# PowerSystem.net
KiCad netlist of a schematic drawn in Altium Designer
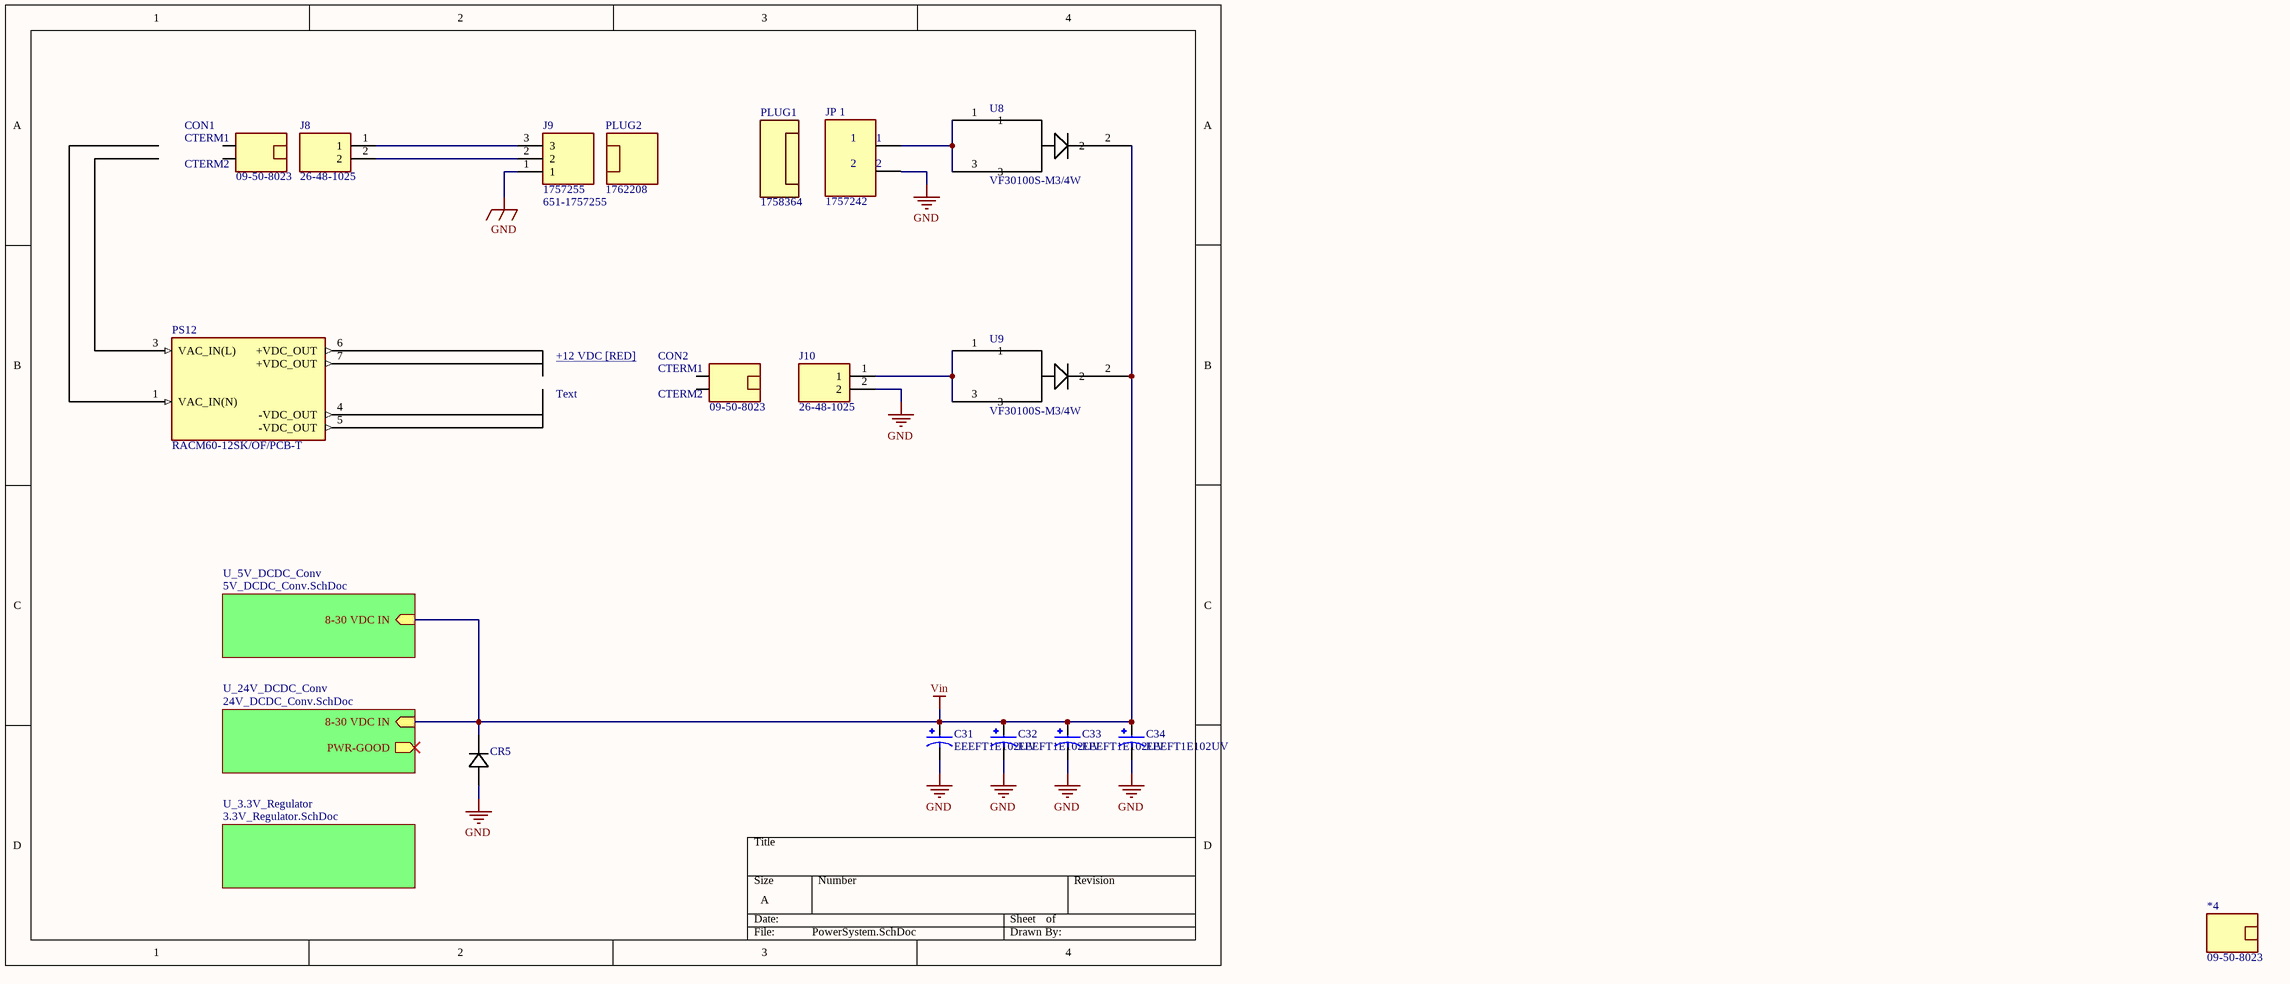
[diagram p0: PowerSystem.SchDoc]

(export (version "E")
  (design (tool "Eeschema 10.0.6"))
  (components
    (comp (ref "*4")
      (value "09-50-8023")
      (footprint "Connector_09-50-8023")
      (description "Connector Housing Receptacle 2 Position 3.96mm Straight Bag")
      (fields (field (name "MANUFACTURER") "Molex"))
      (libsource (lib "") (part "09-50-8023_1"))
    )
    (comp (ref "C31")
      (value "EEEFT1E102UV")
      (footprint "CAP_EEEFT1E102UV")
      (fields (field (name "MP") "EEE-FT1E102UV") (field (name "MF") "Panasonic Electronic Components"))
      (libsource (lib "EEEFT1E102UV") (part "EEEFT1E102UV"))
    )
    (comp (ref "C32")
      (value "EEEFT1E102UV")
      (footprint "CAP_EEEFT1E102UV")
      (fields (field (name "MP") "EEE-FT1E102UV") (field (name "MF") "Panasonic Electronic Components"))
      (libsource (lib "EEEFT1E102UV") (part "EEEFT1E102UV"))
    )
    (comp (ref "C33")
      (value "EEEFT1E102UV")
      (footprint "CAP_EEEFT1E102UV")
      (fields (field (name "MP") "EEE-FT1E102UV") (field (name "MF") "Panasonic Electronic Components"))
      (libsource (lib "EEEFT1E102UV") (part "EEEFT1E102UV"))
    )
    (comp (ref "C34")
      (value "EEEFT1E102UV")
      (footprint "CAP_EEEFT1E102UV")
      (fields (field (name "MP") "EEE-FT1E102UV") (field (name "MF") "Panasonic Electronic Components"))
      (libsource (lib "EEEFT1E102UV") (part "EEEFT1E102UV"))
    )
    (comp (ref "CON1")
      (value "09-50-8023")
      (footprint "Connector_09-50-8023")
      (description "Connector Housing Receptacle 2 Position 3.96mm Straight Bag")
      (fields (field (name "MANUFACTURER") "Molex"))
      (libsource (lib "SamacSys") (part "09-50-8023"))
    )
    (comp (ref "CON2")
      (value "09-50-8023")
      (footprint "Connector_09-50-8023")
      (description "Connector Housing Receptacle 2 Position 3.96mm Straight Bag")
      (fields (field (name "MANUFACTURER") "Molex"))
      (libsource (lib "SamacSys") (part "09-50-8023"))
    )
    (comp (ref "CR5")
      (value "1KSMB39CA")
      (footprint "1KSMBSeries_LTF")
      (description "No Description Available")
      (fields (field (name "COPYRIGHT") "Copyright (C) 2021 Ultra Librarian. All rights reserved."))
      (libsource (lib "1KSMB39CA") (part "1KSMB39CA"))
    )
    (comp (ref "J8")
      (value "26-48-1025")
      (footprint "SHDR2W155P0X396_1X2_732X902X1468P")
      (description "Connector")
      (fields (field (name "MOUSER PART NUMBER") "538-26-48-1025"))
      (libsource (lib "SamacSys") (part "26-48-1025"))
    )
    (comp (ref "J9")
      (value "1757255")
      (footprint "SHDRRA3W103P0X508_1X3_1724X1200X875P")
      (description "Connector")
      (fields
        (field (name "MOUSER PART NUMBER") "651-1757255")
        (field (name "SUPPLIER PART NUMBER 1") "651-1757255")
      )
      (libsource (lib "SamacSys") (part "1757255"))
    )
    (comp (ref "J10")
      (value "26-48-1025")
      (footprint "SHDR2W155P0X396_1X2_732X902X1468P")
      (description "Connector")
      (fields (field (name "MOUSER PART NUMBER") "538-26-48-1025"))
      (libsource (lib "SamacSys") (part "26-48-1025"))
    )
    (comp (ref "JP 1")
      (value "1757242")
      (footprint "PHOENIX_1757242")
      (fields (field (name "DIGI-KEY_PART_NUMBER") "277-1106-ND") (field (name "MF") "Phoenix Contact"))
      (libsource (lib "Phoenix_1757242") (part "1757242"))
    )
    (comp (ref "PLUG1")
      (value "1758364")
      (footprint "Connector_1758364")
      (description "Conn Terminal Block F 2 POS 5.08mm Screw RA Cable Mount 12A")
      (fields (field (name "MANUFACTURER") "Phoenix Contact") (field (name "VOLTAGE") "300V"))
      (libsource (lib "SamacSys") (part "1758364"))
    )
    (comp (ref "PLUG2")
      (value "1762208")
      (footprint "Connector_1762208")
      (description "Plug, Terminal Block; 12 A; 250 V; 5.08 mm; 3 position, screw, Pre-Printed")
      (fields (field (name "MANUFACTURER") "Phoenix Contact") (field (name "VOLTAGE") "300V"))
      (libsource (lib "SamacSys") (part "1762208"))
    )
    (comp (ref "PS12")
      (value "RACM60-12SK/OF/PCB-T")
      (footprint "CONV_RACM60-12SK/OF/PCB-T")
      (description "Open Frame AC DC Converters 1 Uitgang 24V 2.5A 80 ~ 264 VAC, 120 ~ 370 VDC Input")
      (libsource (lib "Supply_RACM60-12SK_OF_PCB-T") (part "RACM60-12SK/OF/PCB-T"))
    )
    (comp (ref "U8")
      (value "VF30100S-M3/4W")
      (footprint "TO_0S-M3/4W_VIS")
      (description "No Description Available")
      (fields (field (name "COPYRIGHT") "Copyright (C) 2021 Ultra Librarian. All rights reserved."))
      (libsource (lib "VF30100S-M3&slash_4W") (part "VF30100S-M3/4W"))
    )
    (comp (ref "U9")
      (value "VF30100S-M3/4W")
      (footprint "TO_0S-M3/4W_VIS")
      (description "No Description Available")
      (fields (field (name "COPYRIGHT") "Copyright (C) 2021 Ultra Librarian. All rights reserved."))
      (libsource (lib "VF30100S-M3&slash_4W") (part "VF30100S-M3/4W"))
    )
  )
  (nets
    (net (code "2") (name "GND") (class "Default")
      (node (ref "C31") (pin "2") (pinfunction "2_2") (pintype "passive"))
      (node (ref "C32") (pin "2") (pinfunction "2_2") (pintype "passive"))
      (node (ref "C33") (pin "2") (pinfunction "2_2") (pintype "passive"))
      (node (ref "C34") (pin "2") (pinfunction "2_2") (pintype "passive"))
      (node (ref "CR5") (pin "2") (pinfunction "12_2") (pintype "passive"))
      (node (ref "J10") (pin "2") (pinfunction "2_2") (pintype "passive"))
      (node (ref "J9") (pin "1") (pinfunction "1_1") (pintype "passive"))
    )
    (net (code "3") (name "Net-(J8-Pad1)") (class "Default")
      (node (ref "J8") (pin "1") (pinfunction "1_1") (pintype "passive"))
      (node (ref "J9") (pin "3") (pinfunction "3_3") (pintype "passive"))
    )
    (net (code "4") (name "Net-(J8-Pad2)") (class "Default")
      (node (ref "J8") (pin "2") (pinfunction "2_2") (pintype "passive"))
      (node (ref "J9") (pin "2") (pinfunction "2_2") (pintype "passive"))
    )
    (net (code "5") (name "Net-(J10-Pad1)") (class "Default")
      (node (ref "J10") (pin "1") (pinfunction "1_1") (pintype "passive"))
      (node (ref "U9") (pin "1") (pinfunction "1_1") (pintype "passive"))
      (node (ref "U9") (pin "3") (pinfunction "3_3") (pintype "passive"))
    )
    (net (code "6") (name "Net-(U8-Pad1)") (class "Default")
      (node (ref "U8") (pin "1") (pinfunction "1_1") (pintype "passive"))
      (node (ref "U8") (pin "3") (pinfunction "3_3") (pintype "passive"))
    )
    (net (code "7") (name "Vin") (class "Default")
      (node (ref "C31") (pin "1") (pinfunction "1_1") (pintype "passive"))
      (node (ref "C32") (pin "1") (pinfunction "1_1") (pintype "passive"))
      (node (ref "C33") (pin "1") (pinfunction "1_1") (pintype "passive"))
      (node (ref "C34") (pin "1") (pinfunction "1_1") (pintype "passive"))
      (node (ref "CR5") (pin "1") (pinfunction "11_1") (pintype "passive"))
      (node (ref "U8") (pin "2") (pinfunction "2_2") (pintype "passive"))
      (node (ref "U9") (pin "2") (pinfunction "2_2") (pintype "passive"))
    )
    (net (code "8") (name "unconnected-(PS12-+VDC_OUT-Pad6)") (class "Default")
      (node (ref "PS12") (pin "6") (pinfunction "+VDC_OUT_6") (pintype "output"))
    )
    (net (code "9") (name "unconnected-(PS12-+VDC_OUT-Pad7)") (class "Default")
      (node (ref "PS12") (pin "7") (pinfunction "+VDC_OUT_7") (pintype "output"))
    )
    (net (code "10") (name "unconnected-(PS12--VDC_OUT-Pad4)") (class "Default")
      (node (ref "PS12") (pin "4") (pinfunction "-VDC_OUT_4") (pintype "output"))
    )
    (net (code "11") (name "unconnected-(PS12--VDC_OUT-Pad5)") (class "Default")
      (node (ref "PS12") (pin "5") (pinfunction "-VDC_OUT_5") (pintype "output"))
    )
    (net (code "12") (name "unconnected-(PS12-VAC_IN(L)-Pad3)") (class "Default")
      (node (ref "PS12") (pin "3") (pinfunction "VAC_IN(L)_3") (pintype "input"))
    )
    (net (code "13") (name "unconnected-(PS12-VAC_IN(N)-Pad1)") (class "Default")
      (node (ref "PS12") (pin "1") (pinfunction "VAC_IN(N)_1") (pintype "input"))
    )
  )
)
